# Light_Curtain_5.net
KiCad netlist of a schematic drawn in EAGLE
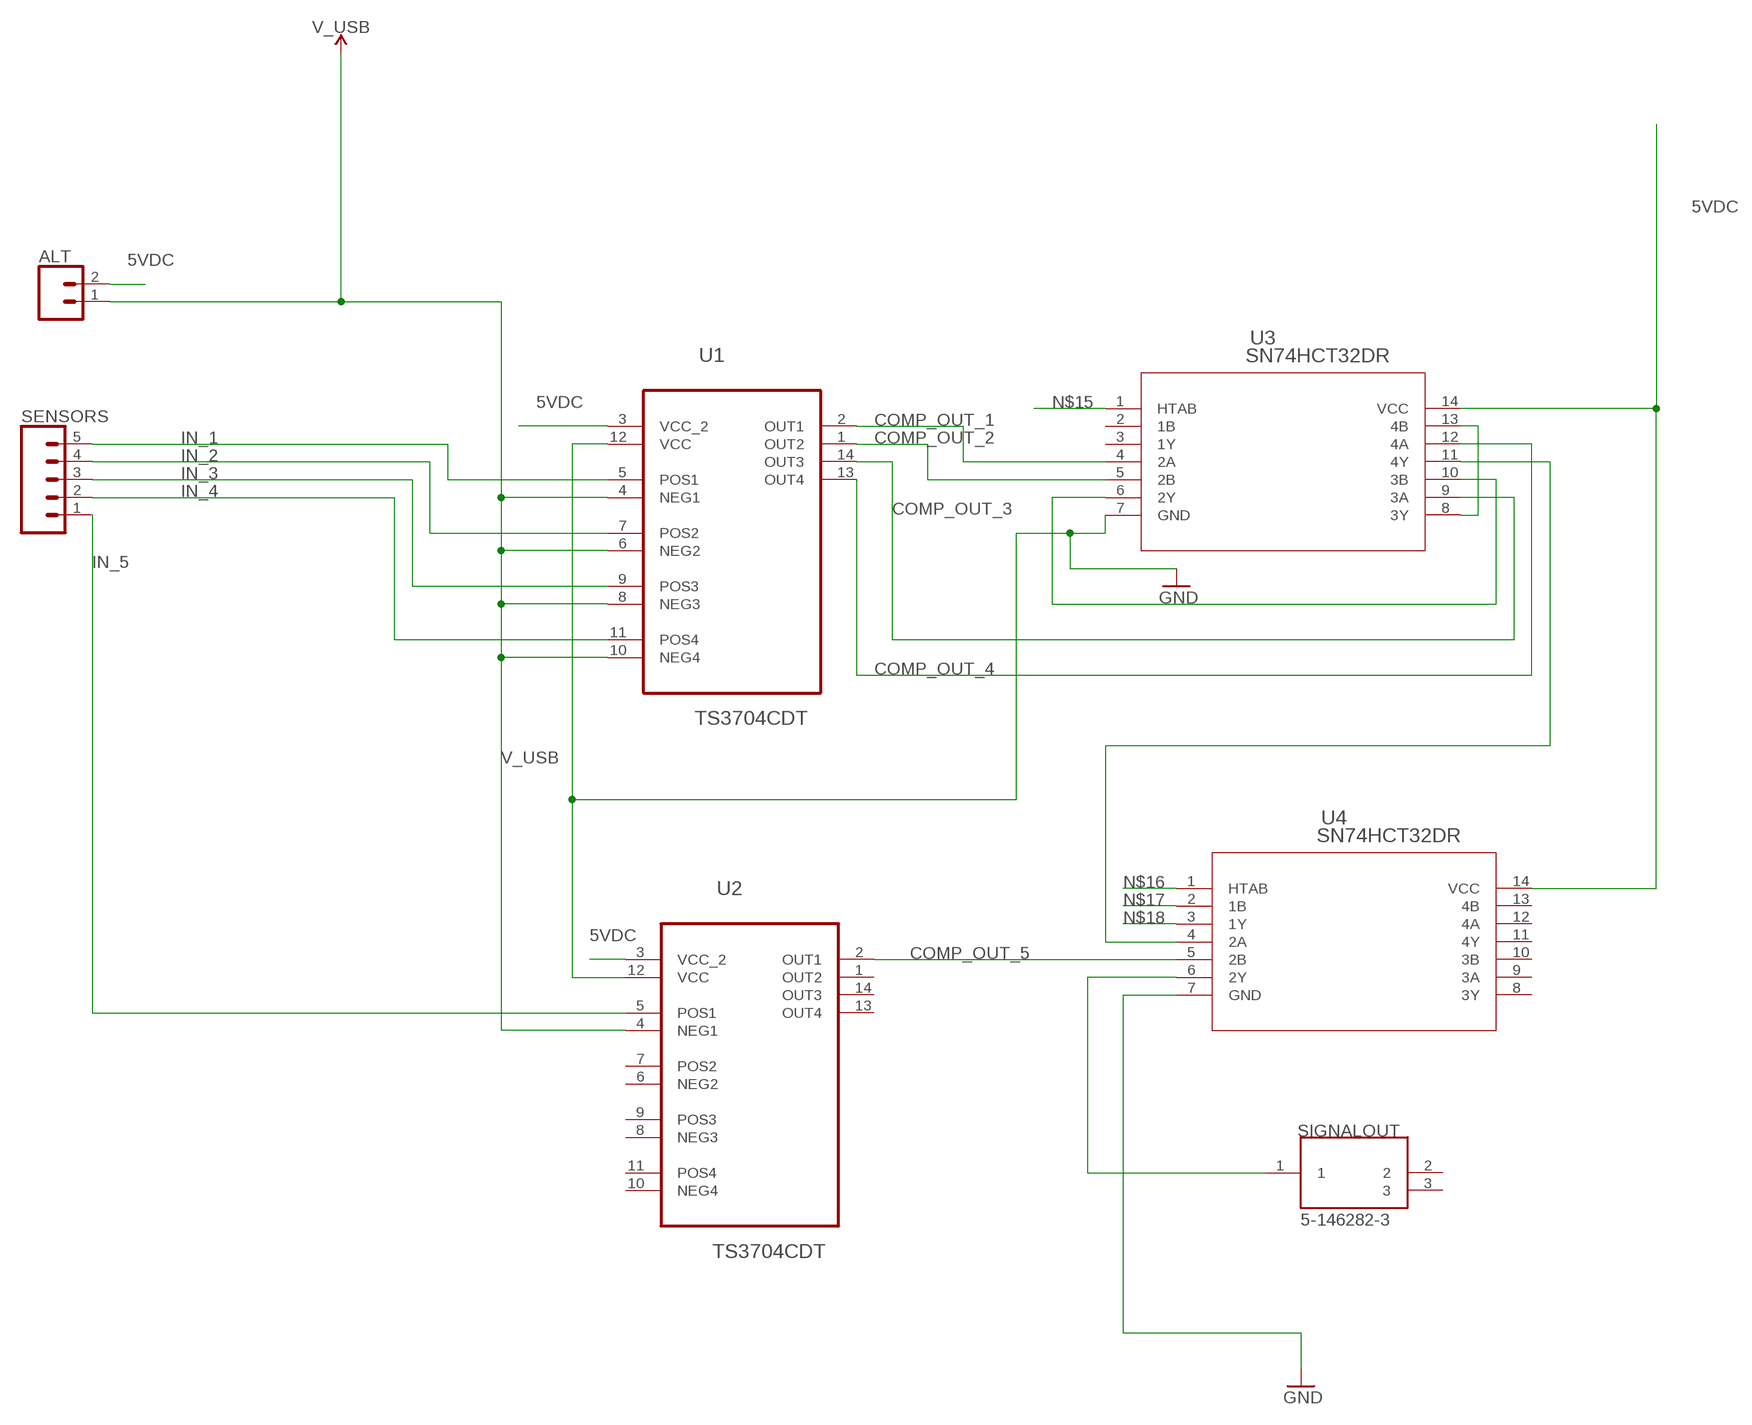
[diagram p0: schematic, sheet 1]

(export (version "E")
  (design (tool "Eeschema 10.0.6"))
  (components
    (comp (ref "ALT")
      (value "CONN_02")
      (footprint "eagle-import:1X02")
      (libsource (lib "eagle-import") (part "CONN_02"))
    )
    (comp (ref "SENSORS")
      (value "CONN_05")
      (footprint "eagle-import:1X05")
      (libsource (lib "eagle-import") (part "CONN_05"))
    )
    (comp (ref "SIGNALOUT")
      (value "5-146282-3")
      (footprint "eagle-import:TE_5-146282-3")
      (fields (field (name "MF") "TE Connectivity"))
      (libsource (lib "eagle-import") (part "5-146282-3"))
    )
    (comp (ref "U1")
      (value "TS3704CDT")
      (footprint "eagle-import:SOIC127P600X175-14N")
      (fields (field (name "MF") "STMicroelectronics") (field (name "MP") "TS3704CD"))
      (libsource (lib "eagle-import") (part "TS3704CDT"))
    )
    (comp (ref "U2")
      (value "TS3704CDT")
      (footprint "eagle-import:SOIC127P600X175-14N")
      (fields (field (name "MF") "STMicroelectronics") (field (name "MP") "TS3704CD"))
      (libsource (lib "eagle-import") (part "TS3704CDT"))
    )
    (comp (ref "U3")
      (value "SN74HCT32DR")
      (footprint "eagle-import:D14")
      (libsource (lib "eagle-import") (part "SN74HCT32DR"))
    )
    (comp (ref "U4")
      (value "SN74HCT32DR")
      (footprint "eagle-import:D14")
      (libsource (lib "eagle-import") (part "SN74HCT32DR"))
    )
  )
  (nets
    (net (code "1") (name "/5VDC") (class "Default")
      (node (ref "ALT") (pin "2") (pinfunction "2_2") (pintype "passive"))
      (node (ref "U1") (pin "3") (pinfunction "VCC_2_3") (pintype "power_in"))
      (node (ref "U2") (pin "3") (pinfunction "VCC_2_3") (pintype "power_in"))
      (node (ref "U3") (pin "14") (pinfunction "VCC_14") (pintype "power_in"))
      (node (ref "U4") (pin "14") (pinfunction "VCC_14") (pintype "power_in"))
    )
    (net (code "2") (name "/COMP_OUT_1") (class "Default")
      (node (ref "U1") (pin "2") (pinfunction "OUT1_2") (pintype "output"))
      (node (ref "U3") (pin "4") (pinfunction "2A_4") (pintype "input"))
    )
    (net (code "3") (name "/COMP_OUT_2") (class "Default")
      (node (ref "U1") (pin "1") (pinfunction "OUT2_1") (pintype "output"))
      (node (ref "U3") (pin "5") (pinfunction "2B_5") (pintype "input"))
    )
    (net (code "4") (name "/COMP_OUT_3") (class "Default")
      (node (ref "U1") (pin "14") (pinfunction "OUT3_14") (pintype "output"))
      (node (ref "U3") (pin "9") (pinfunction "3A_9") (pintype "input"))
    )
    (net (code "5") (name "/COMP_OUT_4") (class "Default")
      (node (ref "U1") (pin "13") (pinfunction "OUT4_13") (pintype "output"))
      (node (ref "U3") (pin "12") (pinfunction "4A_12") (pintype "input"))
    )
    (net (code "6") (name "/COMP_OUT_5") (class "Default")
      (node (ref "U2") (pin "2") (pinfunction "OUT1_2") (pintype "output"))
      (node (ref "U4") (pin "5") (pinfunction "2B_5") (pintype "input"))
    )
    (net (code "7") (name "/IN_1") (class "Default")
      (node (ref "SENSORS") (pin "5") (pinfunction "5_5") (pintype "passive"))
      (node (ref "U1") (pin "5") (pinfunction "POS1_5") (pintype "input"))
    )
    (net (code "8") (name "/IN_2") (class "Default")
      (node (ref "SENSORS") (pin "4") (pinfunction "4_4") (pintype "passive"))
      (node (ref "U1") (pin "7") (pinfunction "POS2_7") (pintype "input"))
    )
    (net (code "9") (name "/IN_3") (class "Default")
      (node (ref "SENSORS") (pin "3") (pinfunction "3_3") (pintype "passive"))
      (node (ref "U1") (pin "9") (pinfunction "POS3_9") (pintype "input"))
    )
    (net (code "10") (name "/IN_4") (class "Default")
      (node (ref "SENSORS") (pin "2") (pinfunction "2_2") (pintype "passive"))
      (node (ref "U1") (pin "11") (pinfunction "POS4_11") (pintype "input"))
    )
    (net (code "11") (name "/IN_5") (class "Default")
      (node (ref "SENSORS") (pin "1") (pinfunction "1_1") (pintype "passive"))
      (node (ref "U2") (pin "5") (pinfunction "POS1_5") (pintype "input"))
    )
    (net (code "12") (name "/N$15") (class "Default")
      (node (ref "U3") (pin "1") (pinfunction "HTAB_1") (pintype "power_in"))
    )
    (net (code "13") (name "/N$16") (class "Default")
      (node (ref "U4") (pin "1") (pinfunction "HTAB_1") (pintype "power_in"))
    )
    (net (code "14") (name "/N$17") (class "Default")
      (node (ref "U4") (pin "2") (pinfunction "1B_2") (pintype "input"))
    )
    (net (code "15") (name "/N$18") (class "Default")
      (node (ref "U4") (pin "3") (pinfunction "1Y_3") (pintype "output"))
    )
    (net (code "16") (name "GND") (class "Default")
      (node (ref "U1") (pin "12") (pinfunction "VCC_12") (pintype "power_in"))
      (node (ref "U2") (pin "12") (pinfunction "VCC_12") (pintype "power_in"))
      (node (ref "U3") (pin "7") (pinfunction "GND_7") (pintype "power_in"))
      (node (ref "U4") (pin "7") (pinfunction "GND_7") (pintype "power_in"))
    )
    (net (code "17") (name "Net-(U3-2Y)") (class "Default")
      (node (ref "U3") (pin "10") (pinfunction "3B_10") (pintype "input"))
      (node (ref "U3") (pin "6") (pinfunction "2Y_6") (pintype "output"))
    )
    (net (code "18") (name "Net-(U3-3Y)") (class "Default")
      (node (ref "U3") (pin "13") (pinfunction "4B_13") (pintype "input"))
      (node (ref "U3") (pin "8") (pinfunction "3Y_8") (pintype "output"))
    )
    (net (code "19") (name "Net-(U3-4Y)") (class "Default")
      (node (ref "U3") (pin "11") (pinfunction "4Y_11") (pintype "output"))
      (node (ref "U4") (pin "4") (pinfunction "2A_4") (pintype "input"))
    )
    (net (code "20") (name "Net-(U4-2Y)") (class "Default")
      (node (ref "SIGNALOUT") (pin "1") (pinfunction "1_1") (pintype "passive"))
      (node (ref "U4") (pin "6") (pinfunction "2Y_6") (pintype "output"))
    )
    (net (code "21") (name "V_USB") (class "Default")
      (node (ref "ALT") (pin "1") (pinfunction "1_1") (pintype "passive"))
      (node (ref "U1") (pin "10") (pinfunction "NEG4_10") (pintype "input"))
      (node (ref "U1") (pin "4") (pinfunction "NEG1_4") (pintype "input"))
      (node (ref "U1") (pin "6") (pinfunction "NEG2_6") (pintype "input"))
      (node (ref "U1") (pin "8") (pinfunction "NEG3_8") (pintype "input"))
      (node (ref "U2") (pin "4") (pinfunction "NEG1_4") (pintype "input"))
    )
    (net (code "22") (name "unconnected-(SIGNALOUT-Pad2)") (class "Default")
      (node (ref "SIGNALOUT") (pin "2") (pinfunction "2_2") (pintype "passive"))
    )
    (net (code "23") (name "unconnected-(SIGNALOUT-Pad3)") (class "Default")
      (node (ref "SIGNALOUT") (pin "3") (pinfunction "3_3") (pintype "passive"))
    )
    (net (code "24") (name "unconnected-(U2-NEG2-Pad6)") (class "Default")
      (node (ref "U2") (pin "6") (pinfunction "NEG2_6") (pintype "input"))
    )
    (net (code "25") (name "unconnected-(U2-NEG3-Pad8)") (class "Default")
      (node (ref "U2") (pin "8") (pinfunction "NEG3_8") (pintype "input"))
    )
    (net (code "26") (name "unconnected-(U2-NEG4-Pad10)") (class "Default")
      (node (ref "U2") (pin "10") (pinfunction "NEG4_10") (pintype "input"))
    )
    (net (code "27") (name "unconnected-(U2-OUT2-Pad1)") (class "Default")
      (node (ref "U2") (pin "1") (pinfunction "OUT2_1") (pintype "output"))
    )
    (net (code "28") (name "unconnected-(U2-OUT3-Pad14)") (class "Default")
      (node (ref "U2") (pin "14") (pinfunction "OUT3_14") (pintype "output"))
    )
    (net (code "29") (name "unconnected-(U2-OUT4-Pad13)") (class "Default")
      (node (ref "U2") (pin "13") (pinfunction "OUT4_13") (pintype "output"))
    )
    (net (code "30") (name "unconnected-(U2-POS2-Pad7)") (class "Default")
      (node (ref "U2") (pin "7") (pinfunction "POS2_7") (pintype "input"))
    )
    (net (code "31") (name "unconnected-(U2-POS3-Pad9)") (class "Default")
      (node (ref "U2") (pin "9") (pinfunction "POS3_9") (pintype "input"))
    )
    (net (code "32") (name "unconnected-(U2-POS4-Pad11)") (class "Default")
      (node (ref "U2") (pin "11") (pinfunction "POS4_11") (pintype "input"))
    )
    (net (code "33") (name "unconnected-(U3-1B-Pad2)") (class "Default")
      (node (ref "U3") (pin "2") (pinfunction "1B_2") (pintype "input"))
    )
    (net (code "34") (name "unconnected-(U3-1Y-Pad3)") (class "Default")
      (node (ref "U3") (pin "3") (pinfunction "1Y_3") (pintype "output"))
    )
    (net (code "35") (name "unconnected-(U4-3A-Pad9)") (class "Default")
      (node (ref "U4") (pin "9") (pinfunction "3A_9") (pintype "input"))
    )
    (net (code "36") (name "unconnected-(U4-3B-Pad10)") (class "Default")
      (node (ref "U4") (pin "10") (pinfunction "3B_10") (pintype "input"))
    )
    (net (code "37") (name "unconnected-(U4-3Y-Pad8)") (class "Default")
      (node (ref "U4") (pin "8") (pinfunction "3Y_8") (pintype "output"))
    )
    (net (code "38") (name "unconnected-(U4-4A-Pad12)") (class "Default")
      (node (ref "U4") (pin "12") (pinfunction "4A_12") (pintype "input"))
    )
    (net (code "39") (name "unconnected-(U4-4B-Pad13)") (class "Default")
      (node (ref "U4") (pin "13") (pinfunction "4B_13") (pintype "input"))
    )
    (net (code "40") (name "unconnected-(U4-4Y-Pad11)") (class "Default")
      (node (ref "U4") (pin "11") (pinfunction "4Y_11") (pintype "output"))
    )
  )
)
